# eagle-schematic-file.net
KiCad netlist of a schematic drawn in EAGLE
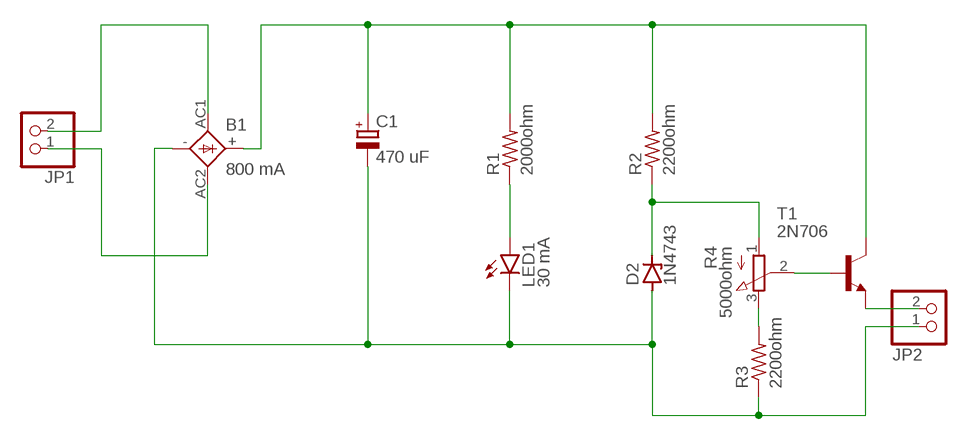
[diagram p0: schematic, sheet 1]

(export (version "E")
  (design (tool "Eeschema 10.0.6"))
  (components
    (comp (ref "B1")
      (value "800 mA")
      (footprint "eagle-import:1KAB")
      (libsource (lib "eagle-import") (part "1KAB"))
    )
    (comp (ref "C1")
      (value "470 uF")
      (footprint "eagle-import:E3,5-10")
      (libsource (lib "eagle-import") (part "CPOL-EUE3.5-10"))
    )
    (comp (ref "D2")
      (value "1N4743")
      (footprint "eagle-import:ZDIO12.5")
      (libsource (lib "eagle-import") (part "ZENER-DIODEZD-12.5"))
    )
    (comp (ref "JP1")
      (value "PINHD-1X2")
      (footprint "eagle-import:1X02")
      (libsource (lib "eagle-import") (part "PINHD-1X2"))
    )
    (comp (ref "JP2")
      (value "PINHD-1X2")
      (footprint "eagle-import:1X02")
      (libsource (lib "eagle-import") (part "PINHD-1X2"))
    )
    (comp (ref "LED1")
      (value "30 mA")
      (footprint "eagle-import:LED5MM")
      (libsource (lib "eagle-import") (part "LED5MM"))
    )
    (comp (ref "R1")
      (value "2000ohm")
      (footprint "eagle-import:0309_12")
      (libsource (lib "eagle-import") (part "R-US_0309/12"))
    )
    (comp (ref "R2")
      (value "2200ohm")
      (footprint "eagle-import:0309_12")
      (libsource (lib "eagle-import") (part "R-US_0309/12"))
    )
    (comp (ref "R3")
      (value "2200ohm")
      (footprint "eagle-import:0309_12")
      (libsource (lib "eagle-import") (part "R-US_0309/12"))
    )
    (comp (ref "R4")
      (value "5000ohm")
      (footprint "eagle-import:3RP_1610N")
      (libsource (lib "eagle-import") (part "3RP/1610N"))
    )
    (comp (ref "T1")
      (value "2N706")
      (footprint "eagle-import:TO18")
      (libsource (lib "eagle-import") (part "2N706"))
    )
  )
  (nets
    (net (code "1") (name "Net-(B1-PadAC1)") (class "Default")
      (node (ref "B1") (pin "AC1") (pinfunction "AC1_AC1") (pintype "passive"))
      (node (ref "JP1") (pin "2") (pinfunction "2_2") (pintype "passive"))
    )
    (net (code "2") (name "Net-(B1-PadAC2)") (class "Default")
      (node (ref "B1") (pin "AC2") (pinfunction "AC2_AC2") (pintype "passive"))
      (node (ref "JP1") (pin "1") (pinfunction "1_1") (pintype "passive"))
    )
    (net (code "3") (name "Net-(LED1-C)") (class "Default")
      (node (ref "B1") (pin "-") (pinfunction "-_-") (pintype "passive"))
      (node (ref "C1") (pin "-") (pinfunction "-_-") (pintype "passive"))
      (node (ref "D2") (pin "A") (pinfunction "A_A") (pintype "passive"))
      (node (ref "JP2") (pin "1") (pinfunction "1_1") (pintype "passive"))
      (node (ref "LED1") (pin "K") (pinfunction "C_K") (pintype "passive"))
      (node (ref "R3") (pin "1") (pinfunction "1_1") (pintype "passive"))
    )
    (net (code "4") (name "Net-(LED1-PadA)") (class "Default")
      (node (ref "LED1") (pin "A") (pinfunction "A_A") (pintype "passive"))
      (node (ref "R1") (pin "1") (pinfunction "1_1") (pintype "passive"))
    )
    (net (code "5") (name "Net-(R4-A)") (class "Default")
      (node (ref "D2") (pin "C") (pinfunction "C_C") (pintype "passive"))
      (node (ref "R2") (pin "1") (pinfunction "1_1") (pintype "passive"))
      (node (ref "R4") (pin "1") (pinfunction "A_1") (pintype "passive"))
    )
    (net (code "6") (name "Net-(R4-E)") (class "Default")
      (node (ref "R3") (pin "2") (pinfunction "2_2") (pintype "passive"))
      (node (ref "R4") (pin "3") (pinfunction "E_3") (pintype "passive"))
    )
    (net (code "7") (name "Net-(R4-S)") (class "Default")
      (node (ref "R4") (pin "2") (pinfunction "S_2") (pintype "passive"))
      (node (ref "T1") (pin "2") (pinfunction "B_2") (pintype "passive"))
    )
    (net (code "8") (name "Net-(T1-C)") (class "Default")
      (node (ref "B1") (pin "+") (pinfunction "+_+") (pintype "passive"))
      (node (ref "C1") (pin "+") (pinfunction "+_+") (pintype "passive"))
      (node (ref "R1") (pin "2") (pinfunction "2_2") (pintype "passive"))
      (node (ref "R2") (pin "2") (pinfunction "2_2") (pintype "passive"))
      (node (ref "T1") (pin "3") (pinfunction "C_3") (pintype "passive"))
    )
    (net (code "9") (name "Net-(T1-E)") (class "Default")
      (node (ref "JP2") (pin "2") (pinfunction "2_2") (pintype "passive"))
      (node (ref "T1") (pin "1") (pinfunction "E_1") (pintype "passive"))
    )
  )
)
